# PowerRails.net
KiCad netlist of a schematic drawn in Altium Designer
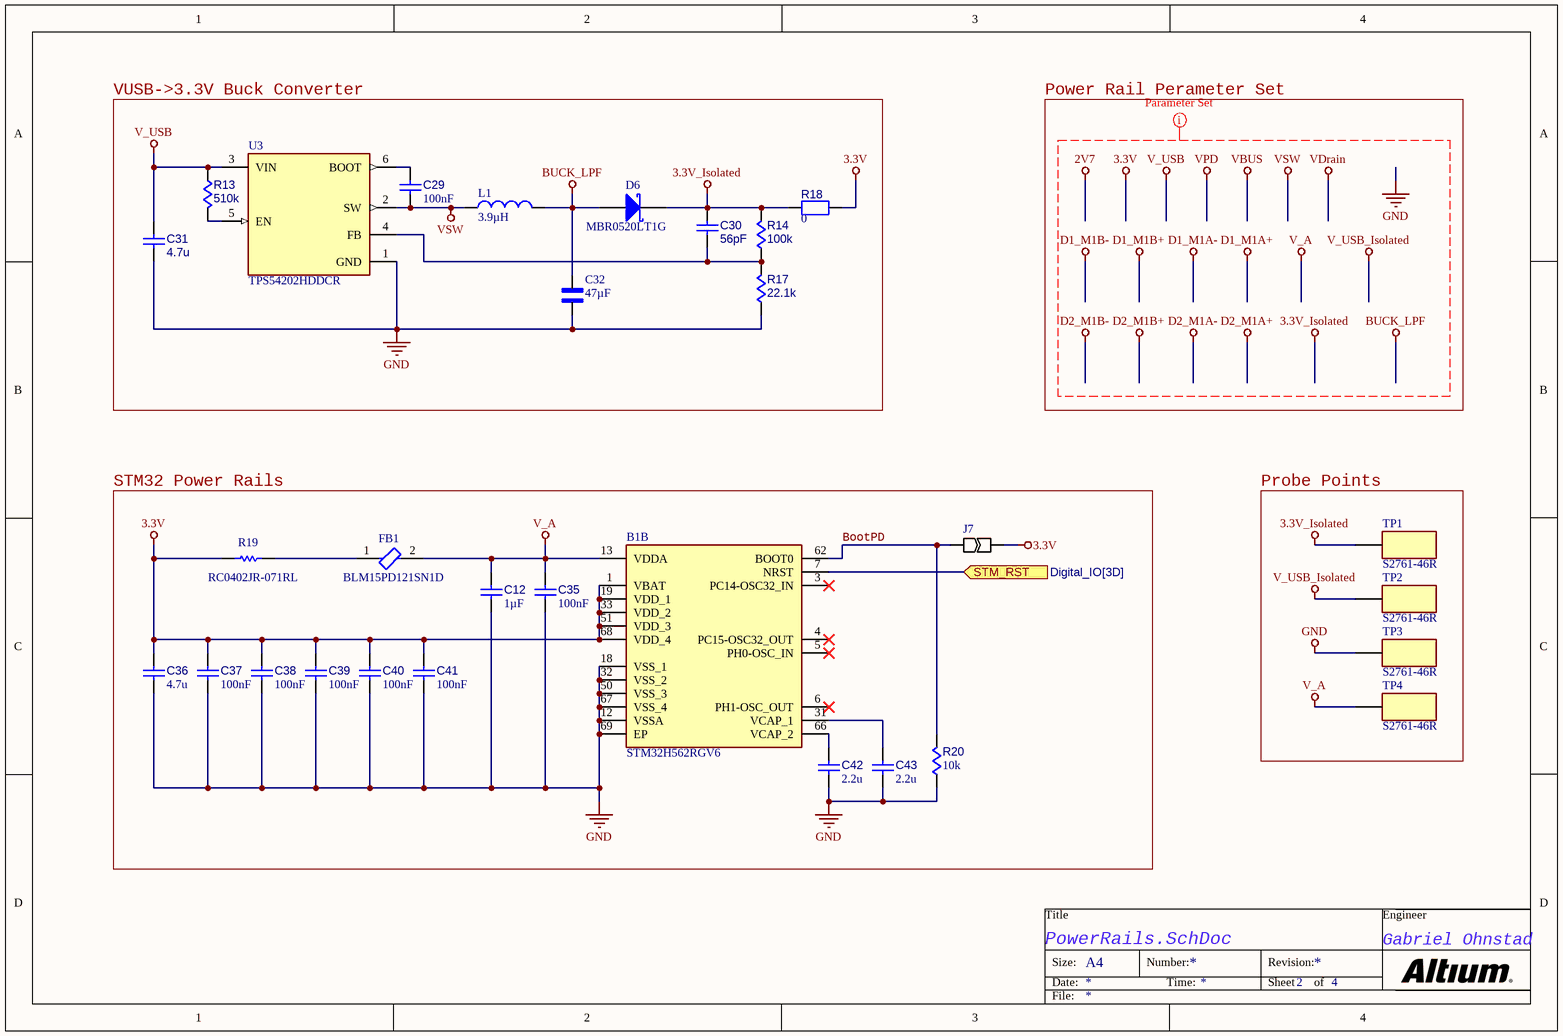
[diagram p0: PowerRails.SchDoc]

(export (version "E")
  (design (tool "Eeschema 10.0.6"))
  (components
    (comp (ref "B1")
      (value "STM32H562RGV6")
      (footprint "QFN40P800X800X100-69N-D")
      (description "MCU 32-bit ARM Cortex M33 RISC 1MB Flash 1.8V/2.5V/3.3V 68-Pin VFQFPN EP Tray")
      (fields
        (field (name "MOUSER PART NUMBER") "511-STM32H563RGV6")
        (field (name "MANUFACTURER_PART_NUMBER") "STM32H563RGV6")
      )
      (libsource (lib "Gabriel A Ohnstad") (part "STM32H563RGV6"))
    )
    (comp (ref "C12")
      (value "1µF")
      (footprint "CAPC1608X94X35NL15T15")
      (description "Chip Capacitor, 1 uF, +/- 10%, 16 V, 0603 (1608 Metric)")
      (fields (field (name "TOLERANCE") "10%") (field (name "Comment") "Capacitor 1 uF +/- 10% 16 V 0603"))
      (libsource (lib "Gabriel A Ohnstad") (part "CAP-NP-2"))
    )
    (comp (ref "C29")
      (value "100nF")
      (footprint "CAPC0402(1005)60_L")
      (description "Chip Capacitor, 100nF +/-20%, 25V, 0402, Thickness 0.6 mm")
      (fields (field (name "TOLERANCE") "10%") (field (name "Comment") "Capacitor 100nF +/-20% 25V 0402"))
      (libsource (lib "Gabriel A Ohnstad") (part "CAP-NP-2"))
    )
    (comp (ref "C30")
      (value "56pF")
      (footprint "CAPC0402(1005)60_L")
      (description "Capacitor, Filter")
      (fields (field (name "TOLERANCE") "5%") (field (name "Comment") "Capacitors,ceramic,0402,5%,56pF"))
      (libsource (lib "Gabriel A Ohnstad") (part "CAP-NP-2"))
    )
    (comp (ref "C31")
      (value "4.7u")
      (footprint "CAPC0805(2012)145_L")
      (description "Capacitor, Decoupling")
      (fields (field (name "Comment") "Capacitors,0805,4.7u"))
      (libsource (lib "Gabriel A Ohnstad") (part "CAP-NP-2"))
    )
    (comp (ref "C32")
      (value "47µF")
      (footprint "CAPC3225X270N")
      (description "SMD Capacitor X5R(EIA) with Capacitance: 47uF Tol. 10%. Rated Voltage: 16Vdc")
      (fields (field (name "MF") "Murata Electronics") (field (name "MP") "GRM32ER61C476KE15L"))
      (libsource (lib "Gabriel A Ohnstad") (part "GRM32ER61C476KE15L"))
    )
    (comp (ref "C35")
      (value "100nF")
      (footprint "CAPC0402(1005)60_L")
      (description "Chip Capacitor, 100nF +/-20%, 25V, 0402, Thickness 0.6 mm")
      (fields (field (name "TOLERANCE") "10%") (field (name "Comment") "Capacitor 100nF +/-20% 25V 0402"))
      (libsource (lib "Gabriel A Ohnstad") (part "CAP-NP-2"))
    )
    (comp (ref "C36")
      (value "4.7u")
      (footprint "CAPC0805(2012)145_L")
      (description "Capacitor, Decoupling")
      (fields (field (name "Comment") "Capacitors,0805,4.7u"))
      (libsource (lib "Gabriel A Ohnstad") (part "CAP-NP-2"))
    )
    (comp (ref "C37")
      (value "100nF")
      (footprint "CAPC0402(1005)60_L")
      (description "Chip Capacitor, 100nF +/-20%, 25V, 0402, Thickness 0.6 mm")
      (fields (field (name "TOLERANCE") "10%") (field (name "Comment") "Capacitor 100nF +/-20% 25V 0402"))
      (libsource (lib "Gabriel A Ohnstad") (part "CAP-NP-2"))
    )
    (comp (ref "C38")
      (value "100nF")
      (footprint "CAPC0402(1005)60_L")
      (description "Chip Capacitor, 100nF +/-20%, 25V, 0402, Thickness 0.6 mm")
      (fields (field (name "TOLERANCE") "10%") (field (name "Comment") "Capacitor 100nF +/-20% 25V 0402"))
      (libsource (lib "Gabriel A Ohnstad") (part "CAP-NP-2"))
    )
    (comp (ref "C39")
      (value "100nF")
      (footprint "CAPC0402(1005)60_L")
      (description "Chip Capacitor, 100nF +/-20%, 25V, 0402, Thickness 0.6 mm")
      (fields (field (name "TOLERANCE") "10%") (field (name "Comment") "Capacitor 100nF +/-20% 25V 0402"))
      (libsource (lib "Gabriel A Ohnstad") (part "CAP-NP-2"))
    )
    (comp (ref "C40")
      (value "100nF")
      (footprint "CAPC0402(1005)60_L")
      (description "Chip Capacitor, 100nF +/-20%, 25V, 0402, Thickness 0.6 mm")
      (fields (field (name "TOLERANCE") "10%") (field (name "Comment") "Capacitor 100nF +/-20% 25V 0402"))
      (libsource (lib "Gabriel A Ohnstad") (part "CAP-NP-2"))
    )
    (comp (ref "C41")
      (value "100nF")
      (footprint "CAPC0402(1005)60_L")
      (description "Chip Capacitor, 100nF +/-20%, 25V, 0402, Thickness 0.6 mm")
      (fields (field (name "TOLERANCE") "10%") (field (name "Comment") "Capacitor 100nF +/-20% 25V 0402"))
      (libsource (lib "Gabriel A Ohnstad") (part "CAP-NP-2"))
    )
    (comp (ref "C42")
      (value "2.2u")
      (footprint "CAPC0805(2012)145_L")
      (description "Capacitor, Charge Pump")
      (fields (field (name "Comment") "Capacitors,0805,2.2u"))
      (libsource (lib "Gabriel A Ohnstad") (part "CAP-NP-2"))
    )
    (comp (ref "C43")
      (value "2.2u")
      (footprint "CAPC0805(2012)145_L")
      (description "Capacitor, Charge Pump")
      (fields (field (name "Comment") "Capacitors,0805,2.2u"))
      (libsource (lib "Gabriel A Ohnstad") (part "CAP-NP-2"))
    )
    (comp (ref "D6")
      (value "MBR0520LT1G")
      (footprint "ONSC-SOD-123-2-425-04_V")
      (description "Schottky Power Rectifier, 20 V, 5.5 A, -65 to 125 degC, 2-Pin SMD, RoHS, Tape and Reel")
      (fields (field (name "MANUFACTURER") "ON Semiconductor"))
      (libsource (lib "Gabriel A Ohnstad") (part "DSKY-AK-2"))
    )
    (comp (ref "FB1")
      (value "BLM15PD121SN1D")
      (footprint "FP-BLM15-0_05-IPC_B")
      (description "Chip Ferrite Bead, 0402, 120Ω @ 100MHz, 0.09Ω, 25%, 1.3A")
      (fields (field (name "TOLERANCE") "25%"))
      (libsource (lib "Altium Content Vault") (part "5f30dd21d616792df468990f7003faa"))
    )
    (comp (ref "J7")
      (value "JUMPER")
      (footprint "JUMPER")
      (libsource (lib "Gabriel A Ohnstad") (part "JUMPER"))
    )
    (comp (ref "L1")
      (value "3.9µH")
      (footprint "SRR5018-3R9Y-Footprint-1")
      (description "Inductor Power Shielded Wirewound 3.9uH 30% 100KHz 8Q-Factor Ferrite 2A 0.055Ohm DCR T/R")
      (fields (field (name "TOLERANCE") "30%") (field (name "Comment") "SRR5018-3R9Y"))
      (libsource (lib "Gabriel A Ohnstad") (part "IND-2"))
    )
    (comp (ref "R13")
      (value "510k")
      (footprint "RESC0402(1005)_L")
      (description "Resistor, Bootstrap")
      (fields (field (name "Comment") "Resistors,0402,510k"))
      (libsource (lib "Gabriel A Ohnstad") (part "RES-2"))
    )
    (comp (ref "R14")
      (value "100k")
      (footprint "RESC0402(1005)_L")
      (description "Resistor")
      (fields (field (name "Comment") "Resistors,0402,100k"))
      (libsource (lib "Gabriel A Ohnstad") (part "RES-2"))
    )
    (comp (ref "R17")
      (value "22.1k")
      (footprint "RESC0402(1005)_L")
      (description "Resistor")
      (fields (field (name "Comment") "Resistors,0402,22.1k"))
      (libsource (lib "Gabriel A Ohnstad") (part "RES-2"))
    )
    (comp (ref "R18")
      (value "0")
      (footprint "RESC0805(2012)_L")
      (description "HCJ Series 0805 Jumper Surface Mount Chip Resistor")
      (fields (field (name "Comment") "HCJ0805ZT0R00"))
      (libsource (lib "") (part "RES-2_1"))
    )
    (comp (ref "R19")
      (value "RC0402JR-071RL")
      (footprint "RESC1005X40X25LL05T10")
      (fields (field (name "MANUFACTURER") "Yageo / Phycomp"))
      (libsource (lib "Altium Content Vault") (part "RES"))
    )
    (comp (ref "R20")
      (value "10k")
      (footprint "RESC0402(1005)_L")
      (description "Resistor, Bootstrap")
      (fields (field (name "Comment") "Resistors,0402,10k"))
      (libsource (lib "Gabriel A Ohnstad") (part "RES-2"))
    )
    (comp (ref "TP1")
      (value "S2761-46R")
      (footprint "HARWIN_S2761-46R")
      (fields (field (name "MF") "{'manufacturer': u'Harwin Inc.'}"))
      (libsource (lib "Gabriel A Ohnstad") (part "S2761-46R"))
    )
    (comp (ref "TP2")
      (value "S2761-46R")
      (footprint "HARWIN_S2761-46R")
      (fields (field (name "MF") "{'manufacturer': u'Harwin Inc.'}"))
      (libsource (lib "Gabriel A Ohnstad") (part "S2761-46R"))
    )
    (comp (ref "TP3")
      (value "S2761-46R")
      (footprint "HARWIN_S2761-46R")
      (fields (field (name "MF") "{'manufacturer': u'Harwin Inc.'}"))
      (libsource (lib "Gabriel A Ohnstad") (part "S2761-46R"))
    )
    (comp (ref "TP4")
      (value "S2761-46R")
      (footprint "HARWIN_S2761-46R")
      (fields (field (name "MF") "{'manufacturer': u'Harwin Inc.'}"))
      (libsource (lib "Gabriel A Ohnstad") (part "S2761-46R"))
    )
    (comp (ref "U3")
      (value "TPS54202HDDCR")
      (footprint "FP-DDC0006A-IPC_C")
      (description "4.5V to 28V Input, 2A Output, Synchronous Step-Down Voltage Converter 6-SOT-23-THIN -40 to 125")
      (libsource (lib "Gabriel A Ohnstad") (part "25a96549b0aea5692a3f4b7350c7a76"))
    )
  )
  (nets
    (net (code "1") (name "/BootPD") (class "Default")
      (node (ref "B1") (pin "62") (pinfunction "BOOT0_62") (pintype "passive"))
      (node (ref "J7") (pin "1") (pinfunction "1_1") (pintype "passive"))
      (node (ref "R20") (pin "2") (pinfunction "2_2") (pintype "passive"))
    )
    (net (code "2") (name "/STM_RST") (class "Default")
      (node (ref "B1") (pin "7") (pinfunction "NRST_7") (pintype "passive"))
    )
    (net (code "4") (name "3.3V") (class "Default")
      (node (ref "B1") (pin "1") (pinfunction "VBAT_1") (pintype "passive"))
      (node (ref "B1") (pin "19") (pinfunction "VDD_1_19") (pintype "passive"))
      (node (ref "B1") (pin "33") (pinfunction "VDD_2_33") (pintype "passive"))
      (node (ref "B1") (pin "51") (pinfunction "VDD_3_51") (pintype "passive"))
      (node (ref "B1") (pin "68") (pinfunction "VDD_4_68") (pintype "passive"))
      (node (ref "C36") (pin "2") (pinfunction "2_2") (pintype "passive"))
      (node (ref "C37") (pin "1") (pinfunction "1_1") (pintype "passive"))
      (node (ref "C38") (pin "1") (pinfunction "1_1") (pintype "passive"))
      (node (ref "C39") (pin "1") (pinfunction "1_1") (pintype "passive"))
      (node (ref "C40") (pin "1") (pinfunction "1_1") (pintype "passive"))
      (node (ref "C41") (pin "1") (pinfunction "1_1") (pintype "passive"))
      (node (ref "J7") (pin "2") (pinfunction "2_2") (pintype "passive"))
      (node (ref "R18") (pin "1") (pinfunction "1_1") (pintype "passive"))
      (node (ref "R19") (pin "1") (pinfunction "1_1") (pintype "passive"))
    )
    (net (code "5") (name "3.3V_Isolated") (class "Default")
      (node (ref "C30") (pin "2") (pinfunction "2_2") (pintype "passive"))
      (node (ref "D6") (pin "2") (pinfunction "K_2") (pintype "passive"))
      (node (ref "R14") (pin "2") (pinfunction "2_2") (pintype "passive"))
      (node (ref "R18") (pin "2") (pinfunction "2_2") (pintype "passive"))
      (node (ref "TP1") (pin "1") (pinfunction "1_1") (pintype "passive"))
    )
    (net (code "6") (name "BUCK_LPF") (class "Default")
      (node (ref "C32") (pin "1") (pinfunction "1_1") (pintype "passive"))
      (node (ref "D6") (pin "1") (pinfunction "A_1") (pintype "passive"))
      (node (ref "L1") (pin "2") (pinfunction "2_2") (pintype "passive"))
    )
    (net (code "15") (name "GND") (class "Default")
      (node (ref "B1") (pin "12") (pinfunction "VSSA_12") (pintype "passive"))
      (node (ref "B1") (pin "18") (pinfunction "VSS_1_18") (pintype "passive"))
      (node (ref "B1") (pin "32") (pinfunction "VSS_2_32") (pintype "passive"))
      (node (ref "B1") (pin "50") (pinfunction "VSS_3_50") (pintype "passive"))
      (node (ref "B1") (pin "67") (pinfunction "VSS_4_67") (pintype "passive"))
      (node (ref "B1") (pin "69") (pinfunction "EP_69") (pintype "passive"))
      (node (ref "C12") (pin "1") (pinfunction "1_1") (pintype "passive"))
      (node (ref "C31") (pin "1") (pinfunction "1_1") (pintype "passive"))
      (node (ref "C32") (pin "2") (pinfunction "2_2") (pintype "passive"))
      (node (ref "C35") (pin "2") (pinfunction "2_2") (pintype "passive"))
      (node (ref "C36") (pin "1") (pinfunction "1_1") (pintype "passive"))
      (node (ref "C37") (pin "2") (pinfunction "2_2") (pintype "passive"))
      (node (ref "C38") (pin "2") (pinfunction "2_2") (pintype "passive"))
      (node (ref "C39") (pin "2") (pinfunction "2_2") (pintype "passive"))
      (node (ref "C40") (pin "2") (pinfunction "2_2") (pintype "passive"))
      (node (ref "C41") (pin "2") (pinfunction "2_2") (pintype "passive"))
      (node (ref "C42") (pin "1") (pinfunction "1_1") (pintype "passive"))
      (node (ref "C43") (pin "1") (pinfunction "1_1") (pintype "passive"))
      (node (ref "R17") (pin "1") (pinfunction "1_1") (pintype "passive"))
      (node (ref "R20") (pin "1") (pinfunction "1_1") (pintype "passive"))
      (node (ref "TP3") (pin "1") (pinfunction "1_1") (pintype "passive"))
      (node (ref "U3") (pin "1") (pinfunction "GND_1") (pintype "power_in"))
    )
    (net (code "16") (name "Net-(B1B-VCAP_1)") (class "Default")
      (node (ref "B1") (pin "31") (pinfunction "VCAP_1_31") (pintype "passive"))
      (node (ref "C43") (pin "2") (pinfunction "2_2") (pintype "passive"))
    )
    (net (code "17") (name "Net-(B1B-VCAP_2)") (class "Default")
      (node (ref "B1") (pin "66") (pinfunction "VCAP_2_66") (pintype "passive"))
      (node (ref "C42") (pin "2") (pinfunction "2_2") (pintype "passive"))
    )
    (net (code "18") (name "Net-(FB1-Pad1)") (class "Default")
      (node (ref "FB1") (pin "1") (pinfunction "1_1") (pintype "passive"))
      (node (ref "R19") (pin "2") (pinfunction "2_2") (pintype "passive"))
    )
    (net (code "19") (name "Net-(U3-BOOT)") (class "Default")
      (node (ref "C29") (pin "2") (pinfunction "2_2") (pintype "passive"))
      (node (ref "U3") (pin "6") (pinfunction "BOOT_6") (pintype "output"))
    )
    (net (code "20") (name "Net-(U3-EN)") (class "Default")
      (node (ref "R13") (pin "2") (pinfunction "2_2") (pintype "passive"))
      (node (ref "U3") (pin "5") (pinfunction "EN_5") (pintype "input"))
    )
    (net (code "21") (name "Net-(U3-FB)") (class "Default")
      (node (ref "C30") (pin "1") (pinfunction "1_1") (pintype "passive"))
      (node (ref "R14") (pin "1") (pinfunction "1_1") (pintype "passive"))
      (node (ref "R17") (pin "2") (pinfunction "2_2") (pintype "passive"))
      (node (ref "U3") (pin "4") (pinfunction "FB_4") (pintype "passive"))
    )
    (net (code "25") (name "VSW") (class "Default")
      (node (ref "C29") (pin "1") (pinfunction "1_1") (pintype "passive"))
      (node (ref "L1") (pin "1") (pinfunction "1_1") (pintype "passive"))
      (node (ref "U3") (pin "2") (pinfunction "SW_2") (pintype "output"))
    )
    (net (code "26") (name "V_A") (class "Default")
      (node (ref "B1") (pin "13") (pinfunction "VDDA_13") (pintype "passive"))
      (node (ref "C12") (pin "2") (pinfunction "2_2") (pintype "passive"))
      (node (ref "C35") (pin "1") (pinfunction "1_1") (pintype "passive"))
      (node (ref "FB1") (pin "2") (pinfunction "2_2") (pintype "passive"))
      (node (ref "TP4") (pin "1") (pinfunction "1_1") (pintype "passive"))
    )
    (net (code "27") (name "V_USB") (class "Default")
      (node (ref "C31") (pin "2") (pinfunction "2_2") (pintype "passive"))
      (node (ref "R13") (pin "1") (pinfunction "1_1") (pintype "passive"))
      (node (ref "U3") (pin "3") (pinfunction "VIN_3") (pintype "power_in"))
    )
    (net (code "28") (name "V_USB_Isolated") (class "Default")
      (node (ref "TP2") (pin "1") (pinfunction "1_1") (pintype "passive"))
    )
    (net (code "29") (name "unconnected-(B1B-PC14-OSC32_IN-Pad3)") (class "Default")
      (node (ref "B1") (pin "3") (pinfunction "PC14-OSC32_IN_3") (pintype "passive+no_connect"))
    )
    (net (code "30") (name "unconnected-(B1B-PC15-OSC32_OUT-Pad4)") (class "Default")
      (node (ref "B1") (pin "4") (pinfunction "PC15-OSC32_OUT_4") (pintype "passive+no_connect"))
    )
    (net (code "31") (name "unconnected-(B1B-PH0-OSC_IN-Pad5)") (class "Default")
      (node (ref "B1") (pin "5") (pinfunction "PH0-OSC_IN_5") (pintype "passive+no_connect"))
    )
    (net (code "32") (name "unconnected-(B1B-PH1-OSC_OUT-Pad6)") (class "Default")
      (node (ref "B1") (pin "6") (pinfunction "PH1-OSC_OUT_6") (pintype "passive+no_connect"))
    )
  )
)
